# 464421_22-01_BBP.net
KiCad netlist of a schematic drawn in Altium Designer
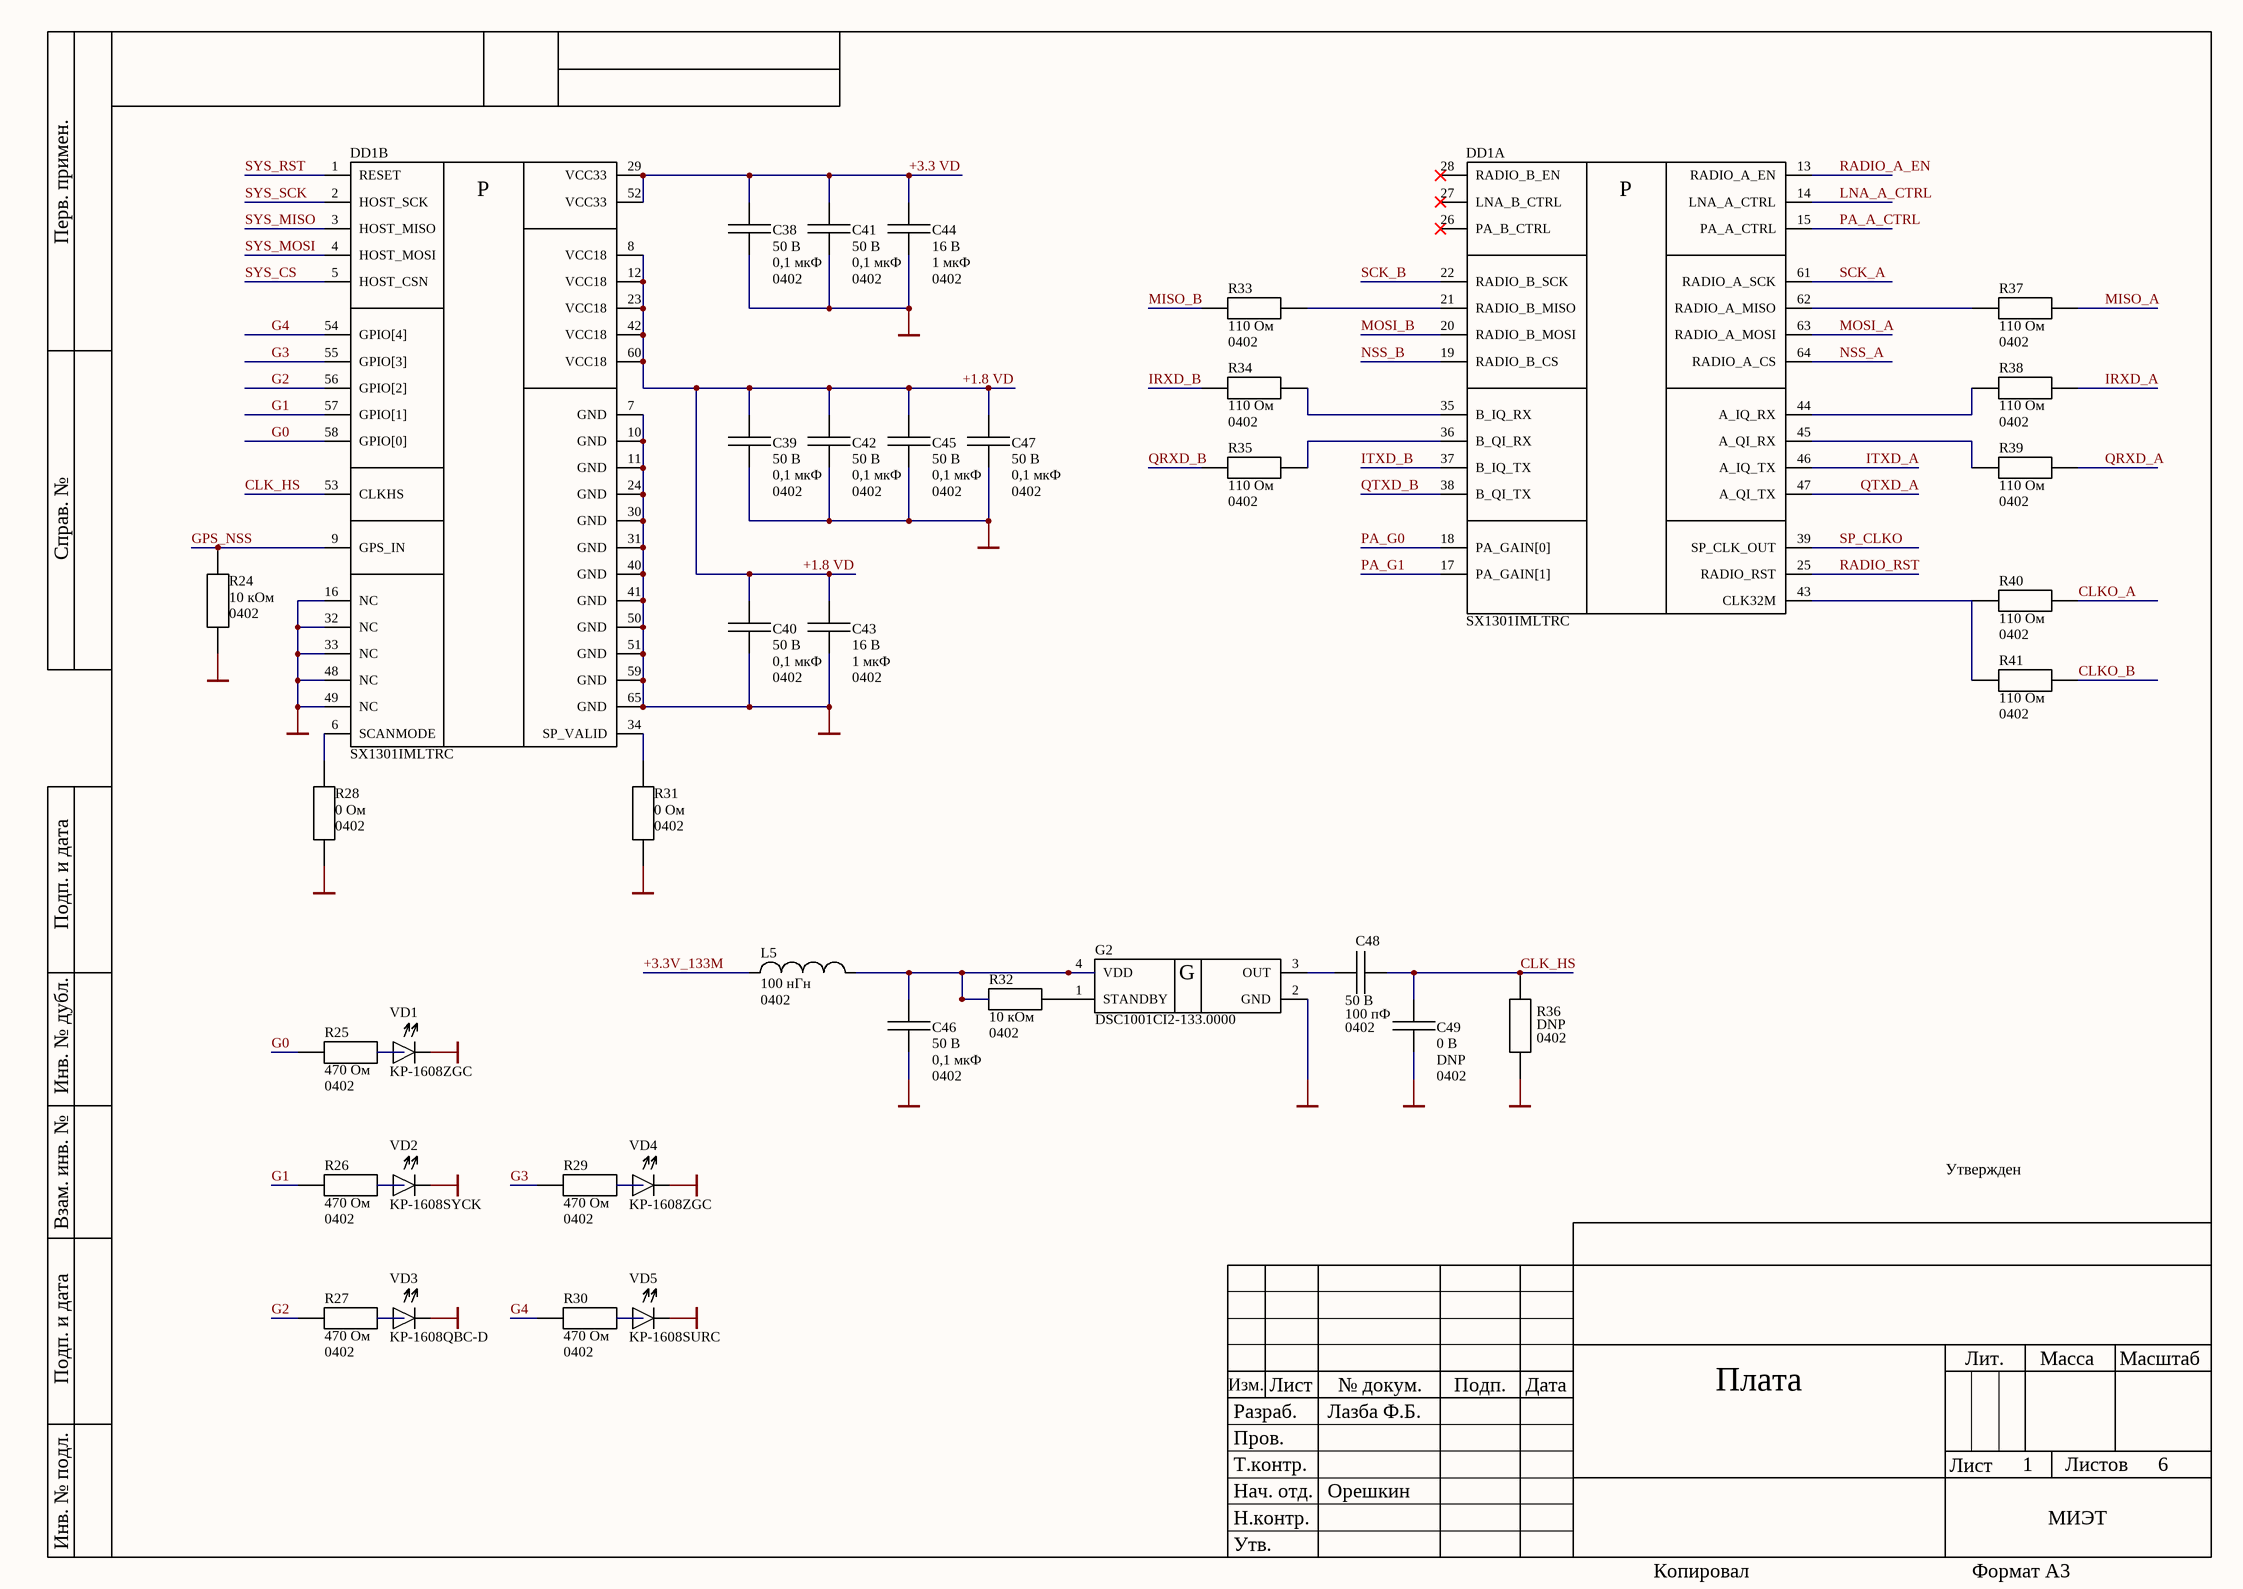
[diagram p0: МПСУ.464421.22-01 BBP.SchDoc]

(export (version "E")
  (design (tool "Eeschema 10.0.6"))
  (components
    (comp (ref "C38")
      (value "0,1 мкФ")
      (footprint "Passive_V2_0:CAPC100X50X55L20N")
      (description "Capacitor 0402")
      (fields
        (field (name "PARTNUMBER") "GRM155R71H104KE14J")
        (field (name "MANUFACTURER") "Murata")
        (field (name "PEAK_CONDITION") "50 В")
        (field (name "PACKAGE") "0402")
        (field (name "DESIGNER") "Свидерский")
      )
      (libsource (lib "Passive_V2_0") (part "C 0402"))
    )
    (comp (ref "C39")
      (value "0,1 мкФ")
      (footprint "Passive_V2_0:CAPC100X50X55L20N")
      (description "Capacitor 0402")
      (fields
        (field (name "PARTNUMBER") "GRM155R71H104KE14J")
        (field (name "MANUFACTURER") "Murata")
        (field (name "PEAK_CONDITION") "50 В")
        (field (name "PACKAGE") "0402")
        (field (name "DESIGNER") "Свидерский")
      )
      (libsource (lib "Passive_V2_0") (part "C 0402"))
    )
    (comp (ref "C40")
      (value "0,1 мкФ")
      (footprint "Passive_V2_0:CAPC100X50X55L20N")
      (description "Capacitor 0402")
      (fields
        (field (name "PARTNUMBER") "GRM155R71H104KE14J")
        (field (name "MANUFACTURER") "Murata")
        (field (name "PEAK_CONDITION") "50 В")
        (field (name "PACKAGE") "0402")
        (field (name "DESIGNER") "Свидерский")
      )
      (libsource (lib "Passive_V2_0") (part "C 0402"))
    )
    (comp (ref "C41")
      (value "0,1 мкФ")
      (footprint "Passive_V2_0:CAPC100X50X55L20N")
      (description "Capacitor 0402")
      (fields
        (field (name "PARTNUMBER") "GRM155R71H104KE14J")
        (field (name "MANUFACTURER") "Murata")
        (field (name "PEAK_CONDITION") "50 В")
        (field (name "PACKAGE") "0402")
        (field (name "DESIGNER") "Свидерский")
      )
      (libsource (lib "Passive_V2_0") (part "C 0402"))
    )
    (comp (ref "C42")
      (value "0,1 мкФ")
      (footprint "Passive_V2_0:CAPC100X50X55L20N")
      (description "Capacitor 0402")
      (fields
        (field (name "PARTNUMBER") "GRM155R71H104KE14J")
        (field (name "MANUFACTURER") "Murata")
        (field (name "PEAK_CONDITION") "50 В")
        (field (name "PACKAGE") "0402")
        (field (name "DESIGNER") "Свидерский")
      )
      (libsource (lib "Passive_V2_0") (part "C 0402"))
    )
    (comp (ref "C43")
      (value "1 мкФ")
      (footprint "Passive_V2_0:CAPC100X50X55L20N")
      (description "Capacitor 0402")
      (fields
        (field (name "PARTNUMBER") "GRM155R61C105KA12D")
        (field (name "MANUFACTURER") "Murata")
        (field (name "PEAK_CONDITION") "16 В")
        (field (name "PACKAGE") "0402")
        (field (name "DESIGNER") "Свидерский")
      )
      (libsource (lib "Passive_V2_0") (part "C 0402"))
    )
    (comp (ref "C44")
      (value "1 мкФ")
      (footprint "Passive_V2_0:CAPC100X50X55L20N")
      (description "Capacitor 0402")
      (fields
        (field (name "PARTNUMBER") "GRM155R61C105KA12D")
        (field (name "MANUFACTURER") "Murata")
        (field (name "PEAK_CONDITION") "16 В")
        (field (name "PACKAGE") "0402")
        (field (name "DESIGNER") "Свидерский")
      )
      (libsource (lib "Passive_V2_0") (part "C 0402"))
    )
    (comp (ref "C45")
      (value "0,1 мкФ")
      (footprint "Passive_V2_0:CAPC100X50X55L20N")
      (description "Capacitor 0402")
      (fields
        (field (name "PARTNUMBER") "GRM155R71H104KE14J")
        (field (name "MANUFACTURER") "Murata")
        (field (name "PEAK_CONDITION") "50 В")
        (field (name "PACKAGE") "0402")
        (field (name "DESIGNER") "Свидерский")
      )
      (libsource (lib "Passive_V2_0") (part "C 0402"))
    )
    (comp (ref "C46")
      (value "0,1 мкФ")
      (footprint "Passive_V2_0:CAPC100X50X55L20N")
      (description "Capacitor 0402")
      (fields
        (field (name "PARTNUMBER") "GRM155R71H104KE14J")
        (field (name "MANUFACTURER") "Murata")
        (field (name "PEAK_CONDITION") "50 В")
        (field (name "PACKAGE") "0402")
        (field (name "DESIGNER") "Свидерский")
      )
      (libsource (lib "Passive_V2_0") (part "C 0402"))
    )
    (comp (ref "C47")
      (value "0,1 мкФ")
      (footprint "Passive_V2_0:CAPC100X50X55L20N")
      (description "Capacitor 0402")
      (fields
        (field (name "PARTNUMBER") "GRM155R71H104KE14J")
        (field (name "MANUFACTURER") "Murata")
        (field (name "PEAK_CONDITION") "50 В")
        (field (name "PACKAGE") "0402")
        (field (name "DESIGNER") "Свидерский")
      )
      (libsource (lib "Passive_V2_0") (part "C 0402"))
    )
    (comp (ref "C48")
      (value "100 пФ")
      (footprint "Passive_V2_0:CAPC100X50X55L20N")
      (description "Capacitor 0402")
      (fields
        (field (name "PARTNUMBER") "GRM1555C1H101JZ01D")
        (field (name "MANUFACTURER") "Murata")
        (field (name "PEAK_CONDITION") "50 В")
        (field (name "PACKAGE") "0402")
        (field (name "DESIGNER") "Свидерский")
      )
      (libsource (lib "Passive_V2_0") (part "C 0402"))
    )
    (comp (ref "C49")
      (value "DNP")
      (footprint "Passive_V2_0:CAPC100X50X55L20N")
      (description "Capacitor 0402")
      (fields
        (field (name "TOLERANCE") "0 %")
        (field (name "PEAK_CONDITION") "0 В")
        (field (name "PACKAGE") "0402")
        (field (name "Comment") "DNP 0402")
        (field (name "DESIGNER") "Свидерский")
      )
      (libsource (lib "Passive_V2_0") (part "C 0402"))
    )
    (comp (ref "DD1")
      (value "SX1301IMLTRC")
      (footprint "IC_V2_0:SX1301IMLTRC")
      (description "LoRa Core™ Digital Baseband Chip for outdoor LoRaWAN® network macro gateways")
      (fields
        (field (name "MANUFACTURER") "Semtech")
        (field (name "PARTNUMBER") "SX1301IMLTRC")
        (field (name "DESIGNER") "Лазба")
      )
      (libsource (lib "IC_V2_0") (part "SX1301IMLTRC"))
    )
    (comp (ref "G2")
      (value "DSC1001CI2-133.0000")
      (footprint "IC_V2_0:DSC1001CI2")
      (description "1.8V-3.3V Low-Power Precision CMOS Oscillators 1-150 MHz Family")
      (fields
        (field (name "MANUFACTURER") "Microchip")
        (field (name "PARTNUMBER") "DSC1001CI2-133.0000")
        (field (name "DESIGNER") "Лазба")
      )
      (libsource (lib "IC_V2_0") (part "DSC1001/3/4***-***.****"))
    )
    (comp (ref "L5")
      (value "100 нГн")
      (footprint "Passive_V2_0:INDC100X50X60L10N")
      (description "Inductor 0402")
      (fields
        (field (name "PARTNUMBER") "LQG15HNR10J02D")
        (field (name "TOLERANCE") "5 %")
        (field (name "PACKAGE") "0402")
        (field (name "DESIGNER") "Свидерский")
      )
      (libsource (lib "Passive_V2_0") (part "L 0402"))
    )
    (comp (ref "R24")
      (value "10 кОм")
      (footprint "Passive_V2_0:RESC100X50X40L25N")
      (description "Resistor 0402")
      (fields
        (field (name "PARTNUMBER") "RI0402L103JT")
        (field (name "TOLERANCE") "5 %")
        (field (name "PACKAGE") "0402")
        (field (name "DESIGNER") "Свидерский")
      )
      (libsource (lib "") (part "R 0402_2"))
    )
    (comp (ref "R25")
      (value "470 Ом")
      (footprint "Passive_V2_0:RESC100X50X40L25N")
      (description "Resistor 0402")
      (fields
        (field (name "PARTNUMBER") "RI0402L471JT")
        (field (name "TOLERANCE") "5 %")
        (field (name "PACKAGE") "0402")
        (field (name "DESIGNER") "Свидерский")
      )
      (libsource (lib "Passive_V2_0") (part "R 0402"))
    )
    (comp (ref "R26")
      (value "470 Ом")
      (footprint "Passive_V2_0:RESC100X50X40L25N")
      (description "Resistor 0402")
      (fields
        (field (name "PARTNUMBER") "RI0402L471JT")
        (field (name "TOLERANCE") "5 %")
        (field (name "PACKAGE") "0402")
        (field (name "DESIGNER") "Свидерский")
      )
      (libsource (lib "Passive_V2_0") (part "R 0402"))
    )
    (comp (ref "R27")
      (value "470 Ом")
      (footprint "Passive_V2_0:RESC100X50X40L25N")
      (description "Resistor 0402")
      (fields
        (field (name "PARTNUMBER") "RI0402L471JT")
        (field (name "TOLERANCE") "5 %")
        (field (name "PACKAGE") "0402")
        (field (name "DESIGNER") "Свидерский")
      )
      (libsource (lib "Passive_V2_0") (part "R 0402"))
    )
    (comp (ref "R28")
      (value "0 Ом")
      (footprint "Passive_V2_0:RESC100X50X40L25N")
      (description "Resistor 0402")
      (fields
        (field (name "PARTNUMBER") "RI0402L000JT")
        (field (name "TOLERANCE") "5 %")
        (field (name "PACKAGE") "0402")
        (field (name "DESIGNER") "Свидерский")
      )
      (libsource (lib "") (part "R 0402_2"))
    )
    (comp (ref "R29")
      (value "470 Ом")
      (footprint "Passive_V2_0:RESC100X50X40L25N")
      (description "Resistor 0402")
      (fields
        (field (name "PARTNUMBER") "RI0402L471JT")
        (field (name "TOLERANCE") "5 %")
        (field (name "PACKAGE") "0402")
        (field (name "DESIGNER") "Свидерский")
      )
      (libsource (lib "Passive_V2_0") (part "R 0402"))
    )
    (comp (ref "R30")
      (value "470 Ом")
      (footprint "Passive_V2_0:RESC100X50X40L25N")
      (description "Resistor 0402")
      (fields
        (field (name "PARTNUMBER") "RI0402L471JT")
        (field (name "TOLERANCE") "5 %")
        (field (name "PACKAGE") "0402")
        (field (name "DESIGNER") "Свидерский")
      )
      (libsource (lib "Passive_V2_0") (part "R 0402"))
    )
    (comp (ref "R31")
      (value "0 Ом")
      (footprint "Passive_V2_0:RESC100X50X40L25N")
      (description "Resistor 0402")
      (fields
        (field (name "PARTNUMBER") "RI0402L000JT")
        (field (name "TOLERANCE") "5 %")
        (field (name "PACKAGE") "0402")
        (field (name "DESIGNER") "Свидерский")
      )
      (libsource (lib "") (part "R 0402_2"))
    )
    (comp (ref "R32")
      (value "10 кОм")
      (footprint "Passive_V2_0:RESC100X50X40L25N")
      (description "Resistor 0402")
      (fields
        (field (name "PARTNUMBER") "RI0402L103JT")
        (field (name "TOLERANCE") "5 %")
        (field (name "PACKAGE") "0402")
        (field (name "DESIGNER") "Свидерский")
      )
      (libsource (lib "Passive_V2_0") (part "R 0402"))
    )
    (comp (ref "R33")
      (value "110 Ом")
      (footprint "Passive_V2_0:RESC100X50X40L25N")
      (description "Resistor 0402")
      (fields
        (field (name "PARTNUMBER") "RC-02U111JT")
        (field (name "TOLERANCE") "5 %")
        (field (name "PACKAGE") "0402")
        (field (name "DESIGNER") "Свидерский")
      )
      (libsource (lib "Passive_V2_0") (part "R 0402"))
    )
    (comp (ref "R34")
      (value "110 Ом")
      (footprint "Passive_V2_0:RESC100X50X40L25N")
      (description "Resistor 0402")
      (fields
        (field (name "PARTNUMBER") "RC-02U111JT")
        (field (name "TOLERANCE") "5 %")
        (field (name "PACKAGE") "0402")
        (field (name "DESIGNER") "Свидерский")
      )
      (libsource (lib "Passive_V2_0") (part "R 0402"))
    )
    (comp (ref "R35")
      (value "110 Ом")
      (footprint "Passive_V2_0:RESC100X50X40L25N")
      (description "Resistor 0402")
      (fields
        (field (name "PARTNUMBER") "RC-02U111JT")
        (field (name "TOLERANCE") "5 %")
        (field (name "PACKAGE") "0402")
        (field (name "DESIGNER") "Свидерский")
      )
      (libsource (lib "Passive_V2_0") (part "R 0402"))
    )
    (comp (ref "R36")
      (value "DNP")
      (footprint "Passive_V2_0:RESC100X50X40L25N")
      (description "Resistor 0402")
      (fields
        (field (name "TOLERANCE") "0 %")
        (field (name "PACKAGE") "0402")
        (field (name "Comment") "DNP 0402")
        (field (name "DESIGNER") "Свидерский")
      )
      (libsource (lib "") (part "R 0402_1"))
    )
    (comp (ref "R37")
      (value "110 Ом")
      (footprint "Passive_V2_0:RESC100X50X40L25N")
      (description "Resistor 0402")
      (fields
        (field (name "PARTNUMBER") "RC-02U111JT")
        (field (name "TOLERANCE") "5 %")
        (field (name "PACKAGE") "0402")
        (field (name "DESIGNER") "Свидерский")
      )
      (libsource (lib "Passive_V2_0") (part "R 0402"))
    )
    (comp (ref "R38")
      (value "110 Ом")
      (footprint "Passive_V2_0:RESC100X50X40L25N")
      (description "Resistor 0402")
      (fields
        (field (name "PARTNUMBER") "RC-02U111JT")
        (field (name "TOLERANCE") "5 %")
        (field (name "PACKAGE") "0402")
        (field (name "DESIGNER") "Свидерский")
      )
      (libsource (lib "Passive_V2_0") (part "R 0402"))
    )
    (comp (ref "R39")
      (value "110 Ом")
      (footprint "Passive_V2_0:RESC100X50X40L25N")
      (description "Resistor 0402")
      (fields
        (field (name "PARTNUMBER") "RC-02U111JT")
        (field (name "TOLERANCE") "5 %")
        (field (name "PACKAGE") "0402")
        (field (name "DESIGNER") "Свидерский")
      )
      (libsource (lib "Passive_V2_0") (part "R 0402"))
    )
    (comp (ref "R40")
      (value "110 Ом")
      (footprint "Passive_V2_0:RESC100X50X40L25N")
      (description "Resistor 0402")
      (fields
        (field (name "PARTNUMBER") "RC-02U111JT")
        (field (name "TOLERANCE") "5 %")
        (field (name "PACKAGE") "0402")
        (field (name "DESIGNER") "Свидерский")
      )
      (libsource (lib "Passive_V2_0") (part "R 0402"))
    )
    (comp (ref "R41")
      (value "110 Ом")
      (footprint "Passive_V2_0:RESC100X50X40L25N")
      (description "Resistor 0402")
      (fields
        (field (name "PARTNUMBER") "RC-02U111JT")
        (field (name "TOLERANCE") "5 %")
        (field (name "PACKAGE") "0402")
        (field (name "DESIGNER") "Свидерский")
      )
      (libsource (lib "Passive_V2_0") (part "R 0402"))
    )
    (comp (ref "VD1")
      (value "KP-1608ZGC")
      (footprint "Discrete_V2_0:KP-1608ZGC")
      (description "1.6X0.8mm SMD CHIP LED LAMP")
      (fields
        (field (name "MANUFACTURER") "Kingbright")
        (field (name "PARTNUMBER") "KP-1608ZGC")
        (field (name "DESIGNER") "Ушакова")
      )
      (libsource (lib "Discrete_V2_0") (part "KP-1608***"))
    )
    (comp (ref "VD2")
      (value "KP-1608SYCK")
      (footprint "Discrete_V2_0:KP-1608ZGC")
      (description "1.6X0.8mm SMD CHIP LED LAMP")
      (fields
        (field (name "MANUFACTURER") "Kingbright")
        (field (name "PARTNUMBER") "KP-1608SYCK")
        (field (name "DESIGNER") "Ушакова")
      )
      (libsource (lib "Discrete_V2_0") (part "KP-1608***"))
    )
    (comp (ref "VD3")
      (value "KP-1608QBC-D")
      (footprint "Discrete_V2_0:KP-1608ZGC")
      (description "1.6X0.8mm SMD CHIP LED LAMP")
      (fields
        (field (name "MANUFACTURER") "Kingbright")
        (field (name "PARTNUMBER") "KP-1608QBC-D")
        (field (name "DESIGNER") "Ушакова")
      )
      (libsource (lib "Discrete_V2_0") (part "KP-1608***"))
    )
    (comp (ref "VD4")
      (value "KP-1608ZGC")
      (footprint "Discrete_V2_0:KP-1608ZGC")
      (description "1.6X0.8mm SMD CHIP LED LAMP")
      (fields
        (field (name "MANUFACTURER") "Kingbright")
        (field (name "PARTNUMBER") "KP-1608ZGC")
        (field (name "DESIGNER") "Ушакова")
      )
      (libsource (lib "Discrete_V2_0") (part "KP-1608***"))
    )
    (comp (ref "VD5")
      (value "KP-1608SURC")
      (footprint "Discrete_V2_0:KP-1608ZGC")
      (description "1.6X0.8mm SMD CHIP LED LAMP")
      (fields
        (field (name "MANUFACTURER") "Kingbright")
        (field (name "PARTNUMBER") "KP-1608SURC")
        (field (name "DESIGNER") "Ушакова")
      )
      (libsource (lib "Discrete_V2_0") (part "KP-1608***"))
    )
  )
  (nets
    (net (code "1") (name "/+1.8 VD") (class "Default")
      (node (ref "C39") (pin "1") (pinfunction "1_1") (pintype "passive"))
      (node (ref "C40") (pin "1") (pinfunction "1_1") (pintype "passive"))
      (node (ref "C42") (pin "1") (pinfunction "1_1") (pintype "passive"))
      (node (ref "C43") (pin "1") (pinfunction "1_1") (pintype "passive"))
      (node (ref "C45") (pin "1") (pinfunction "1_1") (pintype "passive"))
      (node (ref "C47") (pin "1") (pinfunction "1_1") (pintype "passive"))
      (node (ref "DD1") (pin "12") (pinfunction "VCC18_12") (pintype "passive"))
      (node (ref "DD1") (pin "23") (pinfunction "VCC18_23") (pintype "passive"))
      (node (ref "DD1") (pin "42") (pinfunction "VCC18_42") (pintype "passive"))
      (node (ref "DD1") (pin "60") (pinfunction "VCC18_60") (pintype "passive"))
      (node (ref "DD1") (pin "8") (pinfunction "VCC18_8") (pintype "passive"))
    )
    (net (code "2") (name "/+3.3 VD") (class "Default")
      (node (ref "C38") (pin "1") (pinfunction "1_1") (pintype "passive"))
      (node (ref "C41") (pin "1") (pinfunction "1_1") (pintype "passive"))
      (node (ref "C44") (pin "1") (pinfunction "1_1") (pintype "passive"))
      (node (ref "DD1") (pin "29") (pinfunction "VCC33_29") (pintype "passive"))
      (node (ref "DD1") (pin "52") (pinfunction "VCC33_52") (pintype "passive"))
    )
    (net (code "3") (name "/+3.3V_133M") (class "Default")
      (node (ref "L5") (pin "1") (pinfunction "1_1") (pintype "passive"))
    )
    (net (code "4") (name "/CLKO_A") (class "Default")
      (node (ref "R40") (pin "2") (pinfunction "2_2") (pintype "passive"))
    )
    (net (code "5") (name "/CLKO_B") (class "Default")
      (node (ref "R41") (pin "2") (pinfunction "2_2") (pintype "passive"))
    )
    (net (code "6") (name "/CLK_HS") (class "Default")
      (node (ref "C48") (pin "2") (pinfunction "2_2") (pintype "passive"))
      (node (ref "C49") (pin "1") (pinfunction "1_1") (pintype "passive"))
      (node (ref "DD1") (pin "53") (pinfunction "CLKHS_53") (pintype "passive"))
      (node (ref "R36") (pin "1") (pinfunction "1_1") (pintype "passive"))
    )
    (net (code "7") (name "/G0") (class "Default")
      (node (ref "DD1") (pin "58") (pinfunction "GPIO[0]_58") (pintype "passive"))
      (node (ref "R25") (pin "1") (pinfunction "1_1") (pintype "passive"))
    )
    (net (code "8") (name "/G1") (class "Default")
      (node (ref "DD1") (pin "57") (pinfunction "GPIO[1]_57") (pintype "passive"))
      (node (ref "R26") (pin "1") (pinfunction "1_1") (pintype "passive"))
    )
    (net (code "9") (name "/G2") (class "Default")
      (node (ref "DD1") (pin "56") (pinfunction "GPIO[2]_56") (pintype "passive"))
      (node (ref "R27") (pin "1") (pinfunction "1_1") (pintype "passive"))
    )
    (net (code "10") (name "/G3") (class "Default")
      (node (ref "DD1") (pin "55") (pinfunction "GPIO[3]_55") (pintype "passive"))
      (node (ref "R29") (pin "1") (pinfunction "1_1") (pintype "passive"))
    )
    (net (code "11") (name "/G4") (class "Default")
      (node (ref "DD1") (pin "54") (pinfunction "GPIO[4]_54") (pintype "passive"))
      (node (ref "R30") (pin "1") (pinfunction "1_1") (pintype "passive"))
    )
    (net (code "12") (name "/GPS_NSS") (class "Default")
      (node (ref "DD1") (pin "9") (pinfunction "GPS_IN_9") (pintype "passive"))
      (node (ref "R24") (pin "2") (pinfunction "2_2") (pintype "passive"))
    )
    (net (code "13") (name "/IRXD_A") (class "Default")
      (node (ref "R38") (pin "2") (pinfunction "2_2") (pintype "passive"))
    )
    (net (code "14") (name "/IRXD_B") (class "Default")
      (node (ref "R34") (pin "1") (pinfunction "1_1") (pintype "passive"))
    )
    (net (code "15") (name "/ITXD_A") (class "Default")
      (node (ref "DD1") (pin "46") (pinfunction "A_IQ_TX_46") (pintype "passive"))
    )
    (net (code "16") (name "/ITXD_B") (class "Default")
      (node (ref "DD1") (pin "37") (pinfunction "B_IQ_TX_37") (pintype "passive"))
    )
    (net (code "17") (name "/LNA_A_CTRL") (class "Default")
      (node (ref "DD1") (pin "14") (pinfunction "LNA_A_CTRL_14") (pintype "passive"))
    )
    (net (code "18") (name "/MISO_A") (class "Default")
      (node (ref "R37") (pin "2") (pinfunction "2_2") (pintype "passive"))
    )
    (net (code "19") (name "/MISO_B") (class "Default")
      (node (ref "R33") (pin "1") (pinfunction "1_1") (pintype "passive"))
    )
    (net (code "20") (name "/MOSI_A") (class "Default")
      (node (ref "DD1") (pin "63") (pinfunction "RADIO_A_MOSI_63") (pintype "passive"))
    )
    (net (code "21") (name "/MOSI_B") (class "Default")
      (node (ref "DD1") (pin "20") (pinfunction "RADIO_B_MOSI_20") (pintype "passive"))
    )
    (net (code "22") (name "/NSS_A") (class "Default")
      (node (ref "DD1") (pin "64") (pinfunction "RADIO_A_CS_64") (pintype "passive"))
    )
    (net (code "23") (name "/NSS_B") (class "Default")
      (node (ref "DD1") (pin "19") (pinfunction "RADIO_B_CS_19") (pintype "passive"))
    )
    (net (code "24") (name "/PA_A_CTRL") (class "Default")
      (node (ref "DD1") (pin "15") (pinfunction "PA_A_CTRL_15") (pintype "passive"))
    )
    (net (code "25") (name "/PA_G0") (class "Default")
      (node (ref "DD1") (pin "18") (pinfunction "PA_GAIN[0]_18") (pintype "passive"))
    )
    (net (code "26") (name "/PA_G1") (class "Default")
      (node (ref "DD1") (pin "17") (pinfunction "PA_GAIN[1]_17") (pintype "passive"))
    )
    (net (code "27") (name "/QRXD_A") (class "Default")
      (node (ref "R39") (pin "2") (pinfunction "2_2") (pintype "passive"))
    )
    (net (code "28") (name "/QRXD_B") (class "Default")
      (node (ref "R35") (pin "1") (pinfunction "1_1") (pintype "passive"))
    )
    (net (code "29") (name "/QTXD_A") (class "Default")
      (node (ref "DD1") (pin "47") (pinfunction "A_QI_TX_47") (pintype "passive"))
    )
    (net (code "30") (name "/QTXD_B") (class "Default")
      (node (ref "DD1") (pin "38") (pinfunction "B_QI_TX_38") (pintype "passive"))
    )
    (net (code "31") (name "/RADIO_A_EN") (class "Default")
      (node (ref "DD1") (pin "13") (pinfunction "RADIO_A_EN_13") (pintype "passive"))
    )
    (net (code "32") (name "/RADIO_RST") (class "Default")
      (node (ref "DD1") (pin "25") (pinfunction "RADIO_RST_25") (pintype "passive"))
    )
    (net (code "33") (name "/SCK_A") (class "Default")
      (node (ref "DD1") (pin "61") (pinfunction "RADIO_A_SCK_61") (pintype "passive"))
    )
    (net (code "34") (name "/SCK_B") (class "Default")
      (node (ref "DD1") (pin "22") (pinfunction "RADIO_B_SCK_22") (pintype "passive"))
    )
    (net (code "35") (name "/SP_CLKO") (class "Default")
      (node (ref "DD1") (pin "39") (pinfunction "SP_CLK_OUT_39") (pintype "passive"))
    )
    (net (code "36") (name "/SYS_CS") (class "Default")
      (node (ref "DD1") (pin "5") (pinfunction "HOST_CSN_5") (pintype "passive"))
    )
    (net (code "37") (name "/SYS_MISO") (class "Default")
      (node (ref "DD1") (pin "3") (pinfunction "HOST_MISO_3") (pintype "passive"))
    )
    (net (code "38") (name "/SYS_MOSI") (class "Default")
      (node (ref "DD1") (pin "4") (pinfunction "HOST_MOSI_4") (pintype "passive"))
    )
    (net (code "39") (name "/SYS_RST") (class "Default")
      (node (ref "DD1") (pin "1") (pinfunction "RESET_1") (pintype "passive"))
    )
    (net (code "40") (name "/SYS_SCK") (class "Default")
      (node (ref "DD1") (pin "2") (pinfunction "HOST_SCK_2") (pintype "passive"))
    )
    (net (code "41") (name "GND") (class "Default")
      (node (ref "C38") (pin "2") (pinfunction "2_2") (pintype "passive"))
      (node (ref "C39") (pin "2") (pinfunction "2_2") (pintype "passive"))
      (node (ref "C40") (pin "2") (pinfunction "2_2") (pintype "passive"))
      (node (ref "C41") (pin "2") (pinfunction "2_2") (pintype "passive"))
      (node (ref "C42") (pin "2") (pinfunction "2_2") (pintype "passive"))
      (node (ref "C43") (pin "2") (pinfunction "2_2") (pintype "passive"))
      (node (ref "C44") (pin "2") (pinfunction "2_2") (pintype "passive"))
      (node (ref "C45") (pin "2") (pinfunction "2_2") (pintype "passive"))
      (node (ref "C46") (pin "2") (pinfunction "2_2") (pintype "passive"))
      (node (ref "C47") (pin "2") (pinfunction "2_2") (pintype "passive"))
      (node (ref "C49") (pin "2") (pinfunction "2_2") (pintype "passive"))
      (node (ref "DD1") (pin "10") (pinfunction "GND_10") (pintype "passive"))
      (node (ref "DD1") (pin "11") (pinfunction "GND_11") (pintype "passive"))
      (node (ref "DD1") (pin "16") (pinfunction "NC_16") (pintype "passive"))
      (node (ref "DD1") (pin "24") (pinfunction "GND_24") (pintype "passive"))
      (node (ref "DD1") (pin "30") (pinfunction "GND_30") (pintype "passive"))
      (node (ref "DD1") (pin "31") (pinfunction "GND_31") (pintype "passive"))
      (node (ref "DD1") (pin "32") (pinfunction "NC_32") (pintype "passive"))
      (node (ref "DD1") (pin "33") (pinfunction "NC_33") (pintype "passive"))
      (node (ref "DD1") (pin "40") (pinfunction "GND_40") (pintype "passive"))
      (node (ref "DD1") (pin "41") (pinfunction "GND_41") (pintype "passive"))
      (node (ref "DD1") (pin "48") (pinfunction "NC_48") (pintype "passive"))
      (node (ref "DD1") (pin "49") (pinfunction "NC_49") (pintype "passive"))
      (node (ref "DD1") (pin "50") (pinfunction "GND_50") (pintype "passive"))
      (node (ref "DD1") (pin "51") (pinfunction "GND_51") (pintype "passive"))
      (node (ref "DD1") (pin "59") (pinfunction "GND_59") (pintype "passive"))
      (node (ref "DD1") (pin "65") (pinfunction "GND_65") (pintype "passive"))
      (node (ref "DD1") (pin "7") (pinfunction "GND_7") (pintype "passive"))
      (node (ref "G2") (pin "2") (pinfunction "GND_2") (pintype "passive"))
      (node (ref "R24") (pin "1") (pinfunction "1_1") (pintype "passive"))
      (node (ref "R28") (pin "1") (pinfunction "1_1") (pintype "passive"))
      (node (ref "R31") (pin "1") (pinfunction "1_1") (pintype "passive"))
      (node (ref "R36") (pin "2") (pinfunction "2_2") (pintype "passive"))
      (node (ref "VD1") (pin "2") (pinfunction "2_2") (pintype "passive"))
      (node (ref "VD2") (pin "2") (pinfunction "2_2") (pintype "passive"))
      (node (ref "VD3") (pin "2") (pinfunction "2_2") (pintype "passive"))
      (node (ref "VD4") (pin "2") (pinfunction "2_2") (pintype "passive"))
      (node (ref "VD5") (pin "2") (pinfunction "2_2") (pintype "passive"))
    )
    (net (code "42") (name "Net-(DD1A-A_IQ_RX)") (class "Default")
      (node (ref "DD1") (pin "44") (pinfunction "A_IQ_RX_44") (pintype "passive"))
      (node (ref "R38") (pin "1") (pinfunction "1_1") (pintype "passive"))
    )
    (net (code "43") (name "Net-(DD1A-A_QI_RX)") (class "Default")
      (node (ref "DD1") (pin "45") (pinfunction "A_QI_RX_45") (pintype "passive"))
      (node (ref "R39") (pin "1") (pinfunction "1_1") (pintype "passive"))
    )
    (net (code "44") (name "Net-(DD1A-B_IQ_RX)") (class "Default")
      (node (ref "DD1") (pin "35") (pinfunction "B_IQ_RX_35") (pintype "passive"))
      (node (ref "R34") (pin "2") (pinfunction "2_2") (pintype "passive"))
    )
    (net (code "45") (name "Net-(DD1A-B_QI_RX)") (class "Default")
      (node (ref "DD1") (pin "36") (pinfunction "B_QI_RX_36") (pintype "passive"))
      (node (ref "R35") (pin "2") (pinfunction "2_2") (pintype "passive"))
    )
    (net (code "46") (name "Net-(DD1A-CLK32M)") (class "Default")
      (node (ref "DD1") (pin "43") (pinfunction "CLK32M_43") (pintype "passive"))
      (node (ref "R40") (pin "1") (pinfunction "1_1") (pintype "passive"))
      (node (ref "R41") (pin "1") (pinfunction "1_1") (pintype "passive"))
    )
    (net (code "47") (name "Net-(DD1A-RADIO_A_MISO)") (class "Default")
      (node (ref "DD1") (pin "62") (pinfunction "RADIO_A_MISO_62") (pintype "passive"))
      (node (ref "R37") (pin "1") (pinfunction "1_1") (pintype "passive"))
    )
    (net (code "48") (name "Net-(DD1A-RADIO_B_MISO)") (class "Default")
      (node (ref "DD1") (pin "21") (pinfunction "RADIO_B_MISO_21") (pintype "passive"))
      (node (ref "R33") (pin "2") (pinfunction "2_2") (pintype "passive"))
    )
    (net (code "49") (name "Net-(DD1B-SCANMODE)") (class "Default")
      (node (ref "DD1") (pin "6") (pinfunction "SCANMODE_6") (pintype "passive"))
      (node (ref "R28") (pin "2") (pinfunction "2_2") (pintype "passive"))
    )
    (net (code "50") (name "Net-(DD1B-SP_VALID)") (class "Default")
      (node (ref "DD1") (pin "34") (pinfunction "SP_VALID_34") (pintype "passive"))
      (node (ref "R31") (pin "2") (pinfunction "2_2") (pintype "passive"))
    )
    (net (code "51") (name "Net-(G2-OUT)") (class "Default")
      (node (ref "C48") (pin "1") (pinfunction "1_1") (pintype "passive"))
      (node (ref "G2") (pin "3") (pinfunction "OUT_3") (pintype "passive"))
    )
    (net (code "52") (name "Net-(G2-STANDBY)") (class "Default")
      (node (ref "G2") (pin "1") (pinfunction "STANDBY_1") (pintype "passive"))
      (node (ref "R32") (pin "2") (pinfunction "2_2") (pintype "passive"))
    )
    (net (code "53") (name "Net-(G2-VDD)") (class "Default")
      (node (ref "C46") (pin "1") (pinfunction "1_1") (pintype "passive"))
      (node (ref "G2") (pin "4") (pinfunction "VDD_4") (pintype "passive"))
      (node (ref "L5") (pin "2") (pinfunction "2_2") (pintype "passive"))
      (node (ref "R32") (pin "1") (pinfunction "1_1") (pintype "passive"))
    )
    (net (code "54") (name "Net-(R25-Pad2)") (class "Default")
      (node (ref "R25") (pin "2") (pinfunction "2_2") (pintype "passive"))
      (node (ref "VD1") (pin "1") (pinfunction "1_1") (pintype "passive"))
    )
    (net (code "55") (name "Net-(R26-Pad2)") (class "Default")
      (node (ref "R26") (pin "2") (pinfunction "2_2") (pintype "passive"))
      (node (ref "VD2") (pin "1") (pinfunction "1_1") (pintype "passive"))
    )
    (net (code "56") (name "Net-(R27-Pad2)") (class "Default")
      (node (ref "R27") (pin "2") (pinfunction "2_2") (pintype "passive"))
      (node (ref "VD3") (pin "1") (pinfunction "1_1") (pintype "passive"))
    )
    (net (code "57") (name "Net-(R29-Pad2)") (class "Default")
      (node (ref "R29") (pin "2") (pinfunction "2_2") (pintype "passive"))
      (node (ref "VD4") (pin "1") (pinfunction "1_1") (pintype "passive"))
    )
    (net (code "58") (name "Net-(R30-Pad2)") (class "Default")
      (node (ref "R30") (pin "2") (pinfunction "2_2") (pintype "passive"))
      (node (ref "VD5") (pin "1") (pinfunction "1_1") (pintype "passive"))
    )
    (net (code "59") (name "unconnected-(DD1A-LNA_B_CTRL-Pad27)") (class "Default")
      (node (ref "DD1") (pin "27") (pinfunction "LNA_B_CTRL_27") (pintype "passive+no_connect"))
    )
    (net (code "60") (name "unconnected-(DD1A-PA_B_CTRL-Pad26)") (class "Default")
      (node (ref "DD1") (pin "26") (pinfunction "PA_B_CTRL_26") (pintype "passive+no_connect"))
    )
    (net (code "61") (name "unconnected-(DD1A-RADIO_B_EN-Pad28)") (class "Default")
      (node (ref "DD1") (pin "28") (pinfunction "RADIO_B_EN_28") (pintype "passive+no_connect"))
    )
  )
)
